# 08-Power_3V3.net
KiCad netlist of a schematic drawn in Altium Designer
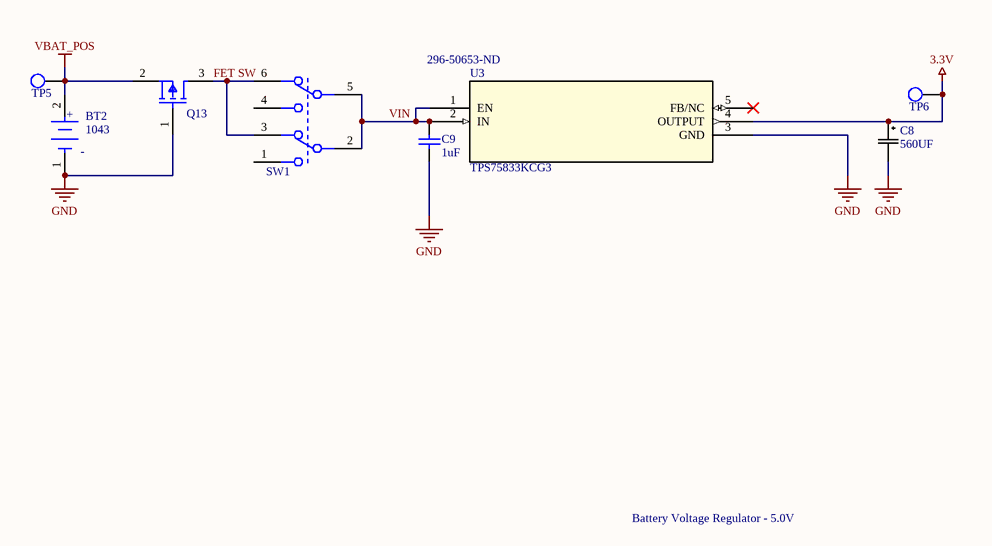
[diagram p0: 08-Power_3V3.SchDoc]

(export (version "E")
  (design (tool "Eeschema 10.0.6"))
  (components
    (comp (ref "BT2")
      (value "1043")
      (footprint "Keystone_1043_0")
      (description "Cylindrical Battery Contacts, Clips, Holders & Springs 18650 PCB PLASTIC BATT HLDR THM 1 CELL")
      (fields (field (name "MANUFACTURER PART NUMBER 1") "1043"))
      (libsource (lib "Battery") (part "1043"))
    )
    (comp (ref "C8")
      (value "560UF")
      (footprint "CAP_RHA/HS_8X7P7_NCH")
      (description "CAP ALUM POLY 560UF 20% 6.3V SMD")
      (fields
        (field (name "MANUFACTURER_PART_NUMBER") "RHA0J561MCN1GS")
        (field (name "COPYRIGHT") "Copyright (C) 2022 Ultra Librarian. All rights reserved.")
      )
      (libsource (lib "team6") (part "RHA0J561MCN1GS"))
    )
    (comp (ref "C9")
      (value "1uF")
      (footprint "CAPC2013X145X50LL20T25")
      (fields (field (name "MANUFACTURER") "Kemet") (field (name "PART NUMBER") "C0805C105K4PACTU"))
      (libsource (lib "Altium Content Vault") (part "CAP"))
    )
    (comp (ref "Q13")
      (value "SSM3J328R,LF")
      (footprint "SOT-23_M")
      (description "MOSFET P-CH 20V 6A SOT23F")
      (libsource (lib "Transistors") (part "SSM3J328R,LF"))
    )
    (comp (ref "SW1")
      (value "JS202011SCQN")
      (footprint "C&K_Components_0_MFG")
      (description "C & K COMPONENTS - JS202011SCQN - SWITCH, DPDT, 0.6A, 6VDC, SMD")
      (libsource (lib "Switches") (part "JS202011SCQN"))
    )
    (comp (ref "TP5")
      (value "TP_1206")
      (footprint "TP-SMC-1206")
      (description "Test Point SMD 1206")
      (fields
        (field (name "MANUFACTURER") "TE Connectivity (Tyco Electronics)")
        (field (name "MANUFACTURER PART NUMBER") "1625854-1")
      )
      (libsource (lib "ECE453-F22-Power") (part "TP_1206"))
    )
    (comp (ref "TP6")
      (value "TP_1206")
      (footprint "TP-SMC-1206")
      (description "Test Point SMD 1206")
      (fields
        (field (name "MANUFACTURER") "TE Connectivity (Tyco Electronics)")
        (field (name "MANUFACTURER PART NUMBER") "1625854-1")
      )
      (libsource (lib "ECE453-F22-Power") (part "TP_1206"))
    )
    (comp (ref "U3")
      (value "TPS75833KCG3")
      (footprint "KC5")
      (description "IC REG LINEAR 3.3V 3A TO220-5")
      (fields
        (field (name "SUPPLIER PART NUMBER 1") "296-50653-ND")
        (field (name "COPYRIGHT") "Copyright (C) 2022 Ultra Librarian. All rights reserved.")
      )
      (libsource (lib "team6") (part "TPS75833KCG3"))
    )
  )
  (nets
    (net (code "1") (name "/FET SW") (class "Default")
      (node (ref "Q13") (pin "3") (pinfunction "Drain_3") (pintype "passive"))
      (node (ref "SW1") (pin "3") (pinfunction "3_3") (pintype "passive"))
      (node (ref "SW1") (pin "6") (pinfunction "6_6") (pintype "passive"))
    )
    (net (code "2") (name "/VIN") (class "Default")
      (node (ref "C9") (pin "1") (pinfunction "1_1") (pintype "passive"))
      (node (ref "SW1") (pin "2") (pinfunction "2_2") (pintype "passive"))
      (node (ref "SW1") (pin "5") (pinfunction "5_5") (pintype "passive"))
      (node (ref "U3") (pin "1") (pinfunction "EN_1") (pintype "passive"))
      (node (ref "U3") (pin "2") (pinfunction "IN_2") (pintype "input"))
    )
    (net (code "3") (name "3.3V") (class "Default")
      (node (ref "C8") (pin "1") (pinfunction "1_1") (pintype "passive"))
      (node (ref "TP6") (pin "1") (pintype "passive"))
      (node (ref "U3") (pin "4") (pinfunction "OUTPUT_4") (pintype "output"))
    )
    (net (code "4") (name "GND") (class "Default")
      (node (ref "BT2") (pin "1") (pinfunction "C_1") (pintype "passive"))
      (node (ref "C8") (pin "2") (pinfunction "2_2") (pintype "passive"))
      (node (ref "C9") (pin "2") (pinfunction "2_2") (pintype "passive"))
      (node (ref "Q13") (pin "1") (pinfunction "Gate_1") (pintype "passive"))
      (node (ref "U3") (pin "3") (pinfunction "GND_3") (pintype "power_in"))
    )
    (net (code "5") (name "VBAT_POS") (class "Default")
      (node (ref "BT2") (pin "2") (pinfunction "A_2") (pintype "passive"))
      (node (ref "Q13") (pin "2") (pinfunction "Source_2") (pintype "passive"))
      (node (ref "TP5") (pin "1") (pintype "passive"))
    )
    (net (code "6") (name "unconnected-(SW1-Pad1)") (class "Default")
      (node (ref "SW1") (pin "1") (pinfunction "1_1") (pintype "passive"))
    )
    (net (code "7") (name "unconnected-(SW1-Pad4)") (class "Default")
      (node (ref "SW1") (pin "4") (pinfunction "4_4") (pintype "passive"))
    )
    (net (code "8") (name "unconnected-(U3-FB{slash}NC-Pad5)") (class "Default")
      (node (ref "U3") (pin "5") (pinfunction "FB/NC_5") (pintype "bidirectional+no_connect"))
    )
  )
)
